# design.net
KiCad netlist of a schematic drawn in Altium Designer
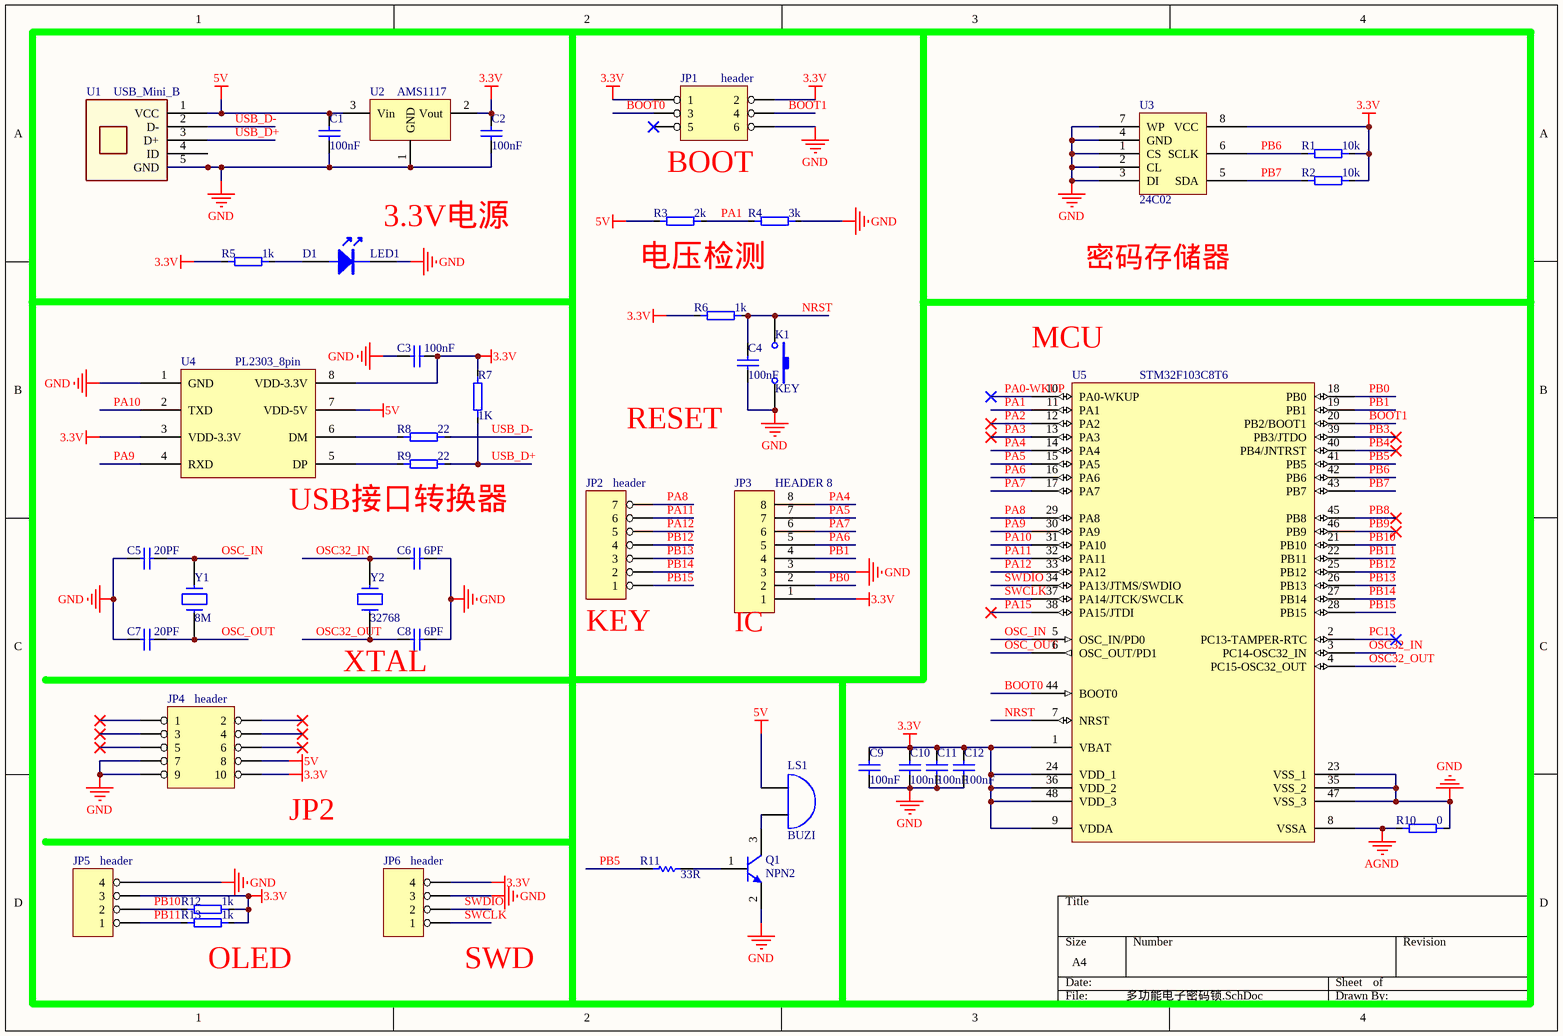
[diagram p0: 多功能电子密码锁.SchDoc]

(export (version "E")
  (design (tool "Eeschema 10.0.6"))
  (components
    (comp (ref "C1")
      (value "100nF")
      (footprint "0603_C")
      (description "Capacitor")
      (fields (field (name "PUBLISHER") "Altium Limited"))
      (libsource (lib "My Footprint") (part "CAP"))
    )
    (comp (ref "C2")
      (value "100nF")
      (footprint "0603_C")
      (description "Capacitor")
      (fields (field (name "PUBLISHER") "Altium Limited"))
      (libsource (lib "My Footprint") (part "CAP"))
    )
    (comp (ref "C3")
      (value "100nF")
      (footprint "0603_C")
      (description "Capacitor")
      (fields (field (name "PUBLISHER") "Altium Limited"))
      (libsource (lib "My Footprint") (part "CAP"))
    )
    (comp (ref "C4")
      (value "100nF")
      (footprint "0603_C")
      (description "Capacitor")
      (fields (field (name "PUBLISHER") "Altium Limited"))
      (libsource (lib "My Footprint") (part "CAP"))
    )
    (comp (ref "C5")
      (value "20PF")
      (footprint "0603_C")
      (description "Capacitor")
      (fields (field (name "PUBLISHER") "Altium Limited"))
      (libsource (lib "My Footprint") (part "CAP"))
    )
    (comp (ref "C6")
      (value "6PF")
      (footprint "0603_C")
      (description "Capacitor")
      (fields (field (name "PUBLISHER") "Altium Limited"))
      (libsource (lib "My Footprint") (part "CAP"))
    )
    (comp (ref "C7")
      (value "20PF")
      (footprint "0603_C")
      (description "Capacitor")
      (fields (field (name "PUBLISHER") "Altium Limited"))
      (libsource (lib "My Footprint") (part "CAP"))
    )
    (comp (ref "C8")
      (value "6PF")
      (footprint "0603_C")
      (description "Capacitor")
      (fields (field (name "PUBLISHER") "Altium Limited"))
      (libsource (lib "My Footprint") (part "CAP"))
    )
    (comp (ref "C9")
      (value "100nF")
      (footprint "0603_C")
      (description "Capacitor")
      (fields (field (name "PUBLISHER") "Altium Limited"))
      (libsource (lib "My Footprint") (part "CAP"))
    )
    (comp (ref "C10")
      (value "100nF")
      (footprint "0603_C")
      (description "Capacitor")
      (fields (field (name "PUBLISHER") "Altium Limited"))
      (libsource (lib "My Footprint") (part "CAP"))
    )
    (comp (ref "C11")
      (value "100nF")
      (footprint "0603_C")
      (description "Capacitor")
      (fields (field (name "PUBLISHER") "Altium Limited"))
      (libsource (lib "My Footprint") (part "CAP"))
    )
    (comp (ref "C12")
      (value "100nF")
      (footprint "0603_C")
      (description "Capacitor")
      (fields (field (name "PUBLISHER") "Altium Limited"))
      (libsource (lib "My Footprint") (part "CAP"))
    )
    (comp (ref "D1") (value "LED1") (footprint "0603_LED") (libsource (lib "My Footprint") (part "LED1")))
    (comp (ref "JP1")
      (value "header")
      (footprint "header2X3")
      (libsource (lib "My Footprint") (part "HEADER 3X2"))
    )
    (comp (ref "JP2")
      (value "header")
      (footprint "header7")
      (libsource (lib "My Footprint") (part "HEADER 7"))
    )
    (comp (ref "JP3") (value "HEADER 8") (footprint "HEADER8") (libsource (lib "RZY21") (part "HEADER 8")))
    (comp (ref "JP4")
      (value "header")
      (footprint "header2X5")
      (libsource (lib "My Footprint") (part "HEADER 5X2"))
    )
    (comp (ref "JP5")
      (value "header")
      (footprint "header4")
      (libsource (lib "My Footprint") (part "HEADER 4"))
    )
    (comp (ref "JP6")
      (value "header")
      (footprint "header4")
      (libsource (lib "My Footprint") (part "HEADER 4"))
    )
    (comp (ref "K1")
      (value "KEY")
      (footprint "KEY_2")
      (description "Switch")
      (fields (field (name "PUBLISHER") "Altium Limited"))
      (libsource (lib "My Footprint") (part "KEY_2"))
    )
    (comp (ref "LS1")
      (value "BUZI")
      (footprint "SPEAK_SMALL")
      (description "Electrical Bell")
      (fields (field (name "PUBLISHER") "Altium Limited"))
      (libsource (lib "Miscellaneous Devices") (part "Bell"))
    )
    (comp (ref "Q1")
      (value "NPN2")
      (footprint "SOT-23-3")
      (description "贴片")
      (libsource (lib "My Footprint") (part "NPN2"))
    )
    (comp (ref "R1") (value "10k") (footprint "RES_0603") (libsource (lib "My Footprint") (part "RES1")))
    (comp (ref "R2") (value "10k") (footprint "RES_0603") (libsource (lib "My Footprint") (part "RES1")))
    (comp (ref "R3") (value "2k") (footprint "RES_0603") (libsource (lib "My Footprint") (part "RES1")))
    (comp (ref "R4") (value "3k") (footprint "RES_0603") (libsource (lib "My Footprint") (part "RES1")))
    (comp (ref "R5") (value "1k") (footprint "RES_0603") (libsource (lib "My Footprint") (part "RES1")))
    (comp (ref "R6") (value "1k") (footprint "RES_0603") (libsource (lib "My Footprint") (part "RES1")))
    (comp (ref "R7") (value "1K") (footprint "RES_0603") (libsource (lib "My Footprint") (part "RES1")))
    (comp (ref "R8") (value "22") (footprint "RES_0603") (libsource (lib "My Footprint") (part "RES1")))
    (comp (ref "R9") (value "22") (footprint "RES_0603") (libsource (lib "My Footprint") (part "RES1")))
    (comp (ref "R10") (value "0") (footprint "RES_0603") (libsource (lib "My Footprint") (part "RES1")))
    (comp (ref "R11")
      (value "33R")
      (footprint "RES_0603")
      (description "Resistor")
      (libsource (lib "RZY21") (part "RES"))
    )
    (comp (ref "R12") (value "1k") (footprint "RES_0603") (libsource (lib "My Footprint") (part "RES1")))
    (comp (ref "R13") (value "1k") (footprint "RES_0603") (libsource (lib "My Footprint") (part "RES1")))
    (comp (ref "U1")
      (value "USB_Mini_B")
      (footprint "USB_MINI_B_SMD")
      (libsource (lib "My Footprint") (part "USB_Mini_B"))
    )
    (comp (ref "U2")
      (value "AMS1117")
      (footprint "SOT-223")
      (description "3.3V电压转换器AMS1117")
      (libsource (lib "My Footprint") (part "AMS1117"))
    )
    (comp (ref "U3") (value "24C02") (footprint "SOP_8") (libsource (lib "My Footprint") (part "24C**")))
    (comp (ref "U4")
      (value "PL2303_8pin")
      (footprint "SOP_8")
      (description "USB转232")
      (libsource (lib "电子系统综合课程设计") (part "PL2303-8pin"))
    )
    (comp (ref "U5")
      (value "STM32F103C8T6")
      (footprint "LQFP48")
      (description "STM32 ARM-based 32-bit MCU with 64 Kbytes Flash, 48-pin LQFP, Industrial Temperature")
      (fields (field (name "PUBLISHER") "Altium Limited"))
      (libsource (lib "My Footprint") (part "STM32F103C8T6"))
    )
    (comp (ref "Y1") (value "8M") (footprint "XTAL_2") (libsource (lib "My Footprint") (part "XTAL32")))
    (comp (ref "Y2") (value "32768") (footprint "XTAL_32") (libsource (lib "My Footprint") (part "XTAL32")))
  )
  (nets
    (net (code "1") (name "/BOOT0") (class "Default")
      (node (ref "JP1") (pin "3") (pinfunction "3_3") (pintype "passive"))
      (node (ref "U5") (pin "44") (pinfunction "BOOT0_44") (pintype "input"))
    )
    (net (code "2") (name "/BOOT1") (class "Default")
      (node (ref "JP1") (pin "4") (pinfunction "4_4") (pintype "passive"))
      (node (ref "U5") (pin "20") (pinfunction "PB2/BOOT1_20") (pintype "bidirectional"))
    )
    (net (code "3") (name "/NRST") (class "Default")
      (node (ref "C4") (pin "1") (pinfunction "1_1") (pintype "passive"))
      (node (ref "K1") (pin "1") (pinfunction "1_1") (pintype "passive"))
      (node (ref "R6") (pin "2") (pinfunction "2_2") (pintype "passive"))
      (node (ref "U5") (pin "7") (pinfunction "NRST_7") (pintype "bidirectional"))
    )
    (net (code "4") (name "/OSC32_IN") (class "Default")
      (node (ref "C6") (pin "2") (pinfunction "2_2") (pintype "passive"))
      (node (ref "U5") (pin "3") (pinfunction "PC14-OSC32_IN_3") (pintype "bidirectional"))
      (node (ref "Y2") (pin "2") (pinfunction "2_2") (pintype "passive"))
    )
    (net (code "5") (name "/OSC32_OUT") (class "Default")
      (node (ref "C8") (pin "2") (pinfunction "2_2") (pintype "passive"))
      (node (ref "U5") (pin "4") (pinfunction "PC15-OSC32_OUT_4") (pintype "bidirectional"))
      (node (ref "Y2") (pin "1") (pinfunction "1_1") (pintype "passive"))
    )
    (net (code "6") (name "/OSC_IN") (class "Default")
      (node (ref "C5") (pin "2") (pinfunction "2_2") (pintype "passive"))
      (node (ref "U5") (pin "5") (pinfunction "OSC_IN/PD0_5") (pintype "input"))
      (node (ref "Y1") (pin "1") (pinfunction "1_1") (pintype "passive"))
    )
    (net (code "7") (name "/OSC_OUT") (class "Default")
      (node (ref "C7") (pin "2") (pinfunction "2_2") (pintype "passive"))
      (node (ref "U5") (pin "6") (pinfunction "OSC_OUT/PD1_6") (pintype "output"))
      (node (ref "Y1") (pin "2") (pinfunction "2_2") (pintype "passive"))
    )
    (net (code "8") (name "/PA0-WKUP") (class "Default")
      (node (ref "U5") (pin "10") (pinfunction "PA0-WKUP_10") (pintype "bidirectional+no_connect"))
    )
    (net (code "9") (name "/PA1") (class "Default")
      (node (ref "R3") (pin "2") (pinfunction "2_2") (pintype "passive"))
      (node (ref "R4") (pin "1") (pinfunction "1_1") (pintype "passive"))
      (node (ref "U5") (pin "11") (pinfunction "PA1_11") (pintype "bidirectional"))
    )
    (net (code "10") (name "/PA2") (class "Default")
      (node (ref "U5") (pin "12") (pinfunction "PA2_12") (pintype "bidirectional+no_connect"))
    )
    (net (code "11") (name "/PA3") (class "Default")
      (node (ref "U5") (pin "13") (pinfunction "PA3_13") (pintype "bidirectional+no_connect"))
    )
    (net (code "12") (name "/PA4") (class "Default")
      (node (ref "JP3") (pin "8") (pinfunction "8_8") (pintype "passive"))
      (node (ref "U5") (pin "14") (pinfunction "PA4_14") (pintype "bidirectional"))
    )
    (net (code "13") (name "/PA5") (class "Default")
      (node (ref "JP3") (pin "7") (pinfunction "7_7") (pintype "passive"))
      (node (ref "U5") (pin "15") (pinfunction "PA5_15") (pintype "bidirectional"))
    )
    (net (code "14") (name "/PA6") (class "Default")
      (node (ref "JP3") (pin "5") (pinfunction "5_5") (pintype "passive"))
      (node (ref "U5") (pin "16") (pinfunction "PA6_16") (pintype "bidirectional"))
    )
    (net (code "15") (name "/PA7") (class "Default")
      (node (ref "JP3") (pin "6") (pinfunction "6_6") (pintype "passive"))
      (node (ref "U5") (pin "17") (pinfunction "PA7_17") (pintype "bidirectional"))
    )
    (net (code "16") (name "/PA8") (class "Default")
      (node (ref "JP2") (pin "7") (pinfunction "7_7") (pintype "passive"))
      (node (ref "U5") (pin "29") (pinfunction "PA8_29") (pintype "bidirectional"))
    )
    (net (code "17") (name "/PA9") (class "Default")
      (node (ref "U4") (pin "4") (pinfunction "RXD_4") (pintype "passive"))
      (node (ref "U5") (pin "30") (pinfunction "PA9_30") (pintype "bidirectional"))
    )
    (net (code "18") (name "/PA10") (class "Default")
      (node (ref "U4") (pin "2") (pinfunction "TXD_2") (pintype "passive"))
      (node (ref "U5") (pin "31") (pinfunction "PA10_31") (pintype "bidirectional"))
    )
    (net (code "19") (name "/PA11") (class "Default")
      (node (ref "JP2") (pin "6") (pinfunction "6_6") (pintype "passive"))
      (node (ref "U5") (pin "32") (pinfunction "PA11_32") (pintype "bidirectional"))
    )
    (net (code "20") (name "/PA12") (class "Default")
      (node (ref "JP2") (pin "5") (pinfunction "5_5") (pintype "passive"))
      (node (ref "U5") (pin "33") (pinfunction "PA12_33") (pintype "bidirectional"))
    )
    (net (code "21") (name "/PA15") (class "Default")
      (node (ref "U5") (pin "38") (pinfunction "PA15/JTDI_38") (pintype "bidirectional+no_connect"))
    )
    (net (code "22") (name "/PB0") (class "Default")
      (node (ref "JP3") (pin "2") (pinfunction "2_2") (pintype "passive"))
      (node (ref "U5") (pin "18") (pinfunction "PB0_18") (pintype "bidirectional"))
    )
    (net (code "23") (name "/PB1") (class "Default")
      (node (ref "JP3") (pin "4") (pinfunction "4_4") (pintype "passive"))
      (node (ref "U5") (pin "19") (pinfunction "PB1_19") (pintype "bidirectional"))
    )
    (net (code "24") (name "/PB3") (class "Default")
      (node (ref "U5") (pin "39") (pinfunction "PB3/JTDO_39") (pintype "bidirectional+no_connect"))
    )
    (net (code "25") (name "/PB4") (class "Default")
      (node (ref "U5") (pin "40") (pinfunction "PB4/JNTRST_40") (pintype "bidirectional+no_connect"))
    )
    (net (code "26") (name "/PB5") (class "Default")
      (node (ref "R11") (pin "2") (pinfunction "2_2") (pintype "passive"))
      (node (ref "U5") (pin "41") (pinfunction "PB5_41") (pintype "bidirectional"))
    )
    (net (code "27") (name "/PB6") (class "Default")
      (node (ref "R1") (pin "1") (pinfunction "1_1") (pintype "passive"))
      (node (ref "U3") (pin "6") (pinfunction "SCLK_6") (pintype "passive"))
      (node (ref "U5") (pin "42") (pinfunction "PB6_42") (pintype "bidirectional"))
    )
    (net (code "28") (name "/PB7") (class "Default")
      (node (ref "R2") (pin "1") (pinfunction "1_1") (pintype "passive"))
      (node (ref "U3") (pin "5") (pinfunction "SDA_5") (pintype "passive"))
      (node (ref "U5") (pin "43") (pinfunction "PB7_43") (pintype "bidirectional"))
    )
    (net (code "29") (name "/PB8") (class "Default")
      (node (ref "U5") (pin "45") (pinfunction "PB8_45") (pintype "bidirectional+no_connect"))
    )
    (net (code "30") (name "/PB9") (class "Default")
      (node (ref "U5") (pin "46") (pinfunction "PB9_46") (pintype "bidirectional+no_connect"))
    )
    (net (code "31") (name "/PB10") (class "Default")
      (node (ref "JP5") (pin "2") (pinfunction "2_2") (pintype "passive"))
      (node (ref "R12") (pin "1") (pinfunction "1_1") (pintype "passive"))
      (node (ref "U5") (pin "21") (pinfunction "PB10_21") (pintype "bidirectional"))
    )
    (net (code "32") (name "/PB11") (class "Default")
      (node (ref "JP5") (pin "1") (pinfunction "1_1") (pintype "passive"))
      (node (ref "R13") (pin "1") (pinfunction "1_1") (pintype "passive"))
      (node (ref "U5") (pin "22") (pinfunction "PB11_22") (pintype "bidirectional"))
    )
    (net (code "33") (name "/PB12") (class "Default")
      (node (ref "JP2") (pin "4") (pinfunction "4_4") (pintype "passive"))
      (node (ref "U5") (pin "25") (pinfunction "PB12_25") (pintype "bidirectional"))
    )
    (net (code "34") (name "/PB13") (class "Default")
      (node (ref "JP2") (pin "3") (pinfunction "3_3") (pintype "passive"))
      (node (ref "U5") (pin "26") (pinfunction "PB13_26") (pintype "bidirectional"))
    )
    (net (code "35") (name "/PB14") (class "Default")
      (node (ref "JP2") (pin "2") (pinfunction "2_2") (pintype "passive"))
      (node (ref "U5") (pin "27") (pinfunction "PB14_27") (pintype "bidirectional"))
    )
    (net (code "36") (name "/PB15") (class "Default")
      (node (ref "JP2") (pin "1") (pinfunction "1_1") (pintype "passive"))
      (node (ref "U5") (pin "28") (pinfunction "PB15_28") (pintype "bidirectional"))
    )
    (net (code "37") (name "/PC13") (class "Default")
      (node (ref "U5") (pin "2") (pinfunction "PC13-TAMPER-RTC_2") (pintype "bidirectional+no_connect"))
    )
    (net (code "38") (name "/SWCLK") (class "Default")
      (node (ref "JP6") (pin "1") (pinfunction "1_1") (pintype "passive"))
      (node (ref "U5") (pin "37") (pinfunction "PA14/JTCK/SWCLK_37") (pintype "bidirectional"))
    )
    (net (code "39") (name "/SWDIO") (class "Default")
      (node (ref "JP6") (pin "2") (pinfunction "2_2") (pintype "passive"))
      (node (ref "U5") (pin "34") (pinfunction "PA13/JTMS/SWDIO_34") (pintype "bidirectional"))
    )
    (net (code "40") (name "/USB_D+") (class "Default")
      (node (ref "R7") (pin "1") (pinfunction "1_1") (pintype "passive"))
      (node (ref "R9") (pin "2") (pinfunction "2_2") (pintype "passive"))
      (node (ref "U1") (pin "3") (pinfunction "D+_3") (pintype "passive"))
    )
    (net (code "41") (name "/USB_D-") (class "Default")
      (node (ref "R8") (pin "2") (pinfunction "2_2") (pintype "passive"))
      (node (ref "U1") (pin "2") (pinfunction "D-_2") (pintype "passive"))
    )
    (net (code "42") (name "3.3V") (class "Default")
      (node (ref "C10") (pin "1") (pinfunction "1_1") (pintype "passive"))
      (node (ref "C11") (pin "1") (pinfunction "1_1") (pintype "passive"))
      (node (ref "C12") (pin "1") (pinfunction "1_1") (pintype "passive"))
      (node (ref "C2") (pin "2") (pinfunction "2_2") (pintype "passive"))
      (node (ref "C3") (pin "1") (pinfunction "1_1") (pintype "passive"))
      (node (ref "C9") (pin "1") (pinfunction "1_1") (pintype "passive"))
      (node (ref "JP1") (pin "1") (pinfunction "1_1") (pintype "passive"))
      (node (ref "JP1") (pin "2") (pinfunction "2_2") (pintype "passive"))
      (node (ref "JP3") (pin "1") (pinfunction "1_1") (pintype "passive"))
      (node (ref "JP4") (pin "10") (pinfunction "10_10") (pintype "passive"))
      (node (ref "JP5") (pin "3") (pinfunction "3_3") (pintype "passive"))
      (node (ref "JP6") (pin "4") (pinfunction "4_4") (pintype "passive"))
      (node (ref "R1") (pin "2") (pinfunction "2_2") (pintype "passive"))
      (node (ref "R12") (pin "2") (pinfunction "2_2") (pintype "passive"))
      (node (ref "R13") (pin "2") (pinfunction "2_2") (pintype "passive"))
      (node (ref "R2") (pin "2") (pinfunction "2_2") (pintype "passive"))
      (node (ref "R5") (pin "1") (pinfunction "1_1") (pintype "passive"))
      (node (ref "R6") (pin "1") (pinfunction "1_1") (pintype "passive"))
      (node (ref "R7") (pin "2") (pinfunction "2_2") (pintype "passive"))
      (node (ref "U2") (pin "2") (pinfunction "Vout_2") (pintype "passive"))
      (node (ref "U3") (pin "8") (pinfunction "VCC_8") (pintype "passive"))
      (node (ref "U4") (pin "3") (pinfunction "VDD-3.3V_3") (pintype "passive"))
      (node (ref "U4") (pin "8") (pinfunction "VDD-3.3V_8") (pintype "passive"))
      (node (ref "U5") (pin "1") (pinfunction "VBAT_1") (pintype "power_in"))
      (node (ref "U5") (pin "24") (pinfunction "VDD_1_24") (pintype "power_in"))
      (node (ref "U5") (pin "36") (pinfunction "VDD_2_36") (pintype "power_in"))
      (node (ref "U5") (pin "48") (pinfunction "VDD_3_48") (pintype "power_in"))
      (node (ref "U5") (pin "9") (pinfunction "VDDA_9") (pintype "power_in"))
    )
    (net (code "43") (name "5V") (class "Default")
      (node (ref "C1") (pin "2") (pinfunction "2_2") (pintype "passive"))
      (node (ref "JP4") (pin "8") (pinfunction "8_8") (pintype "passive"))
      (node (ref "LS1") (pin "1") (pinfunction "A_1") (pintype "passive"))
      (node (ref "R3") (pin "1") (pinfunction "1_1") (pintype "passive"))
      (node (ref "U1") (pin "1") (pinfunction "VCC_1") (pintype "passive"))
      (node (ref "U2") (pin "3") (pinfunction "Vin_3") (pintype "passive"))
      (node (ref "U4") (pin "7") (pinfunction "VDD-5V_7") (pintype "passive"))
    )
    (net (code "44") (name "AGND") (class "Default")
      (node (ref "R10") (pin "1") (pinfunction "1_1") (pintype "passive"))
      (node (ref "U5") (pin "8") (pinfunction "VSSA_8") (pintype "power_in"))
    )
    (net (code "45") (name "GND") (class "Default")
      (node (ref "C1") (pin "1") (pinfunction "1_1") (pintype "passive"))
      (node (ref "C10") (pin "2") (pinfunction "2_2") (pintype "passive"))
      (node (ref "C11") (pin "2") (pinfunction "2_2") (pintype "passive"))
      (node (ref "C12") (pin "2") (pinfunction "2_2") (pintype "passive"))
      (node (ref "C2") (pin "1") (pinfunction "1_1") (pintype "passive"))
      (node (ref "C3") (pin "2") (pinfunction "2_2") (pintype "passive"))
      (node (ref "C4") (pin "2") (pinfunction "2_2") (pintype "passive"))
      (node (ref "C5") (pin "1") (pinfunction "1_1") (pintype "passive"))
      (node (ref "C6") (pin "1") (pinfunction "1_1") (pintype "passive"))
      (node (ref "C7") (pin "1") (pinfunction "1_1") (pintype "passive"))
      (node (ref "C8") (pin "1") (pinfunction "1_1") (pintype "passive"))
      (node (ref "C9") (pin "2") (pinfunction "2_2") (pintype "passive"))
      (node (ref "D1") (pin "2") (pinfunction "K_2") (pintype "passive"))
      (node (ref "JP1") (pin "6") (pinfunction "6_6") (pintype "passive"))
      (node (ref "JP3") (pin "3") (pinfunction "3_3") (pintype "passive"))
      (node (ref "JP4") (pin "7") (pinfunction "7_7") (pintype "passive"))
      (node (ref "JP4") (pin "9") (pinfunction "9_9") (pintype "passive"))
      (node (ref "JP5") (pin "4") (pinfunction "4_4") (pintype "passive"))
      (node (ref "JP6") (pin "3") (pinfunction "3_3") (pintype "passive"))
      (node (ref "K1") (pin "2") (pinfunction "2_2") (pintype "passive"))
      (node (ref "Q1") (pin "2") (pinfunction "E_2") (pintype "passive"))
      (node (ref "R10") (pin "2") (pinfunction "2_2") (pintype "passive"))
      (node (ref "R4") (pin "2") (pinfunction "2_2") (pintype "passive"))
      (node (ref "U1") (pin "5") (pinfunction "GND_5") (pintype "passive"))
      (node (ref "U2") (pin "1") (pinfunction "GND_1") (pintype "passive"))
      (node (ref "U3") (pin "1") (pinfunction "CS_1") (pintype "passive"))
      (node (ref "U3") (pin "2") (pinfunction "CL_2") (pintype "passive"))
      (node (ref "U3") (pin "3") (pinfunction "DI_3") (pintype "passive"))
      (node (ref "U3") (pin "4") (pinfunction "GND_4") (pintype "passive"))
      (node (ref "U3") (pin "7") (pinfunction "WP_7") (pintype "passive"))
      (node (ref "U4") (pin "1") (pinfunction "GND_1") (pintype "passive"))
      (node (ref "U5") (pin "23") (pinfunction "VSS_1_23") (pintype "power_in"))
      (node (ref "U5") (pin "35") (pinfunction "VSS_2_35") (pintype "power_in"))
      (node (ref "U5") (pin "47") (pinfunction "VSS_3_47") (pintype "power_in"))
    )
    (net (code "46") (name "Net-(D1-A)") (class "Default")
      (node (ref "D1") (pin "1") (pinfunction "A_1") (pintype "passive"))
      (node (ref "R5") (pin "2") (pinfunction "2_2") (pintype "passive"))
    )
    (net (code "47") (name "Net-(LS1-B)") (class "Default")
      (node (ref "LS1") (pin "2") (pinfunction "B_2") (pintype "passive"))
      (node (ref "Q1") (pin "3") (pinfunction "C_3") (pintype "passive"))
    )
    (net (code "48") (name "Net-(Q1-B)") (class "Default")
      (node (ref "Q1") (pin "1") (pinfunction "B_1") (pintype "passive"))
      (node (ref "R11") (pin "1") (pinfunction "1_1") (pintype "passive"))
    )
    (net (code "49") (name "Net-(U4-DM)") (class "Default")
      (node (ref "R8") (pin "1") (pinfunction "1_1") (pintype "passive"))
      (node (ref "U4") (pin "6") (pinfunction "DM_6") (pintype "passive"))
    )
    (net (code "50") (name "Net-(U4-DP)") (class "Default")
      (node (ref "R9") (pin "1") (pinfunction "1_1") (pintype "passive"))
      (node (ref "U4") (pin "5") (pinfunction "DP_5") (pintype "passive"))
    )
    (net (code "51") (name "unconnected-(JP1-Pad5)") (class "Default")
      (node (ref "JP1") (pin "5") (pinfunction "5_5") (pintype "passive+no_connect"))
    )
    (net (code "52") (name "unconnected-(JP4-Pad1)") (class "Default")
      (node (ref "JP4") (pin "1") (pinfunction "1_1") (pintype "passive+no_connect"))
    )
    (net (code "53") (name "unconnected-(JP4-Pad2)") (class "Default")
      (node (ref "JP4") (pin "2") (pinfunction "2_2") (pintype "passive+no_connect"))
    )
    (net (code "54") (name "unconnected-(JP4-Pad3)") (class "Default")
      (node (ref "JP4") (pin "3") (pinfunction "3_3") (pintype "passive+no_connect"))
    )
    (net (code "55") (name "unconnected-(JP4-Pad4)") (class "Default")
      (node (ref "JP4") (pin "4") (pinfunction "4_4") (pintype "passive+no_connect"))
    )
    (net (code "56") (name "unconnected-(JP4-Pad5)") (class "Default")
      (node (ref "JP4") (pin "5") (pinfunction "5_5") (pintype "passive+no_connect"))
    )
    (net (code "57") (name "unconnected-(JP4-Pad6)") (class "Default")
      (node (ref "JP4") (pin "6") (pinfunction "6_6") (pintype "passive+no_connect"))
    )
    (net (code "58") (name "unconnected-(U1-ID-Pad4)") (class "Default")
      (node (ref "U1") (pin "4") (pinfunction "ID_4") (pintype "passive"))
    )
  )
)
